# schema.net
KiCad netlist of a schematic drawn in EAGLE
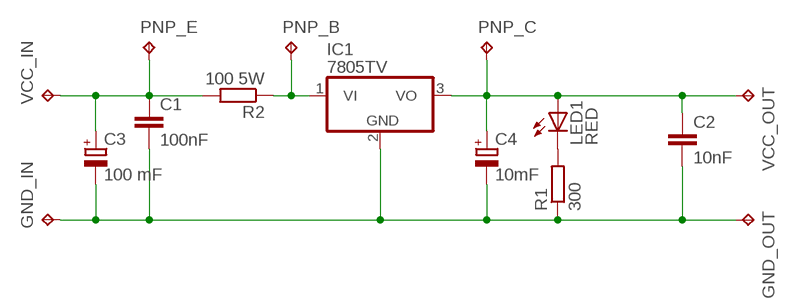
[diagram p0: schematic, sheet 1]

(export (version "E")
  (design (tool "Eeschema 10.0.6"))
  (components
    (comp (ref "C1")
      (value "100nF")
      (footprint "eagle-import:C2.5-4")
      (libsource (lib "eagle-import") (part "C2.5/4"))
    )
    (comp (ref "C2")
      (value "10nF")
      (footprint "eagle-import:C2.5-4")
      (libsource (lib "eagle-import") (part "C2.5/4"))
    )
    (comp (ref "C3")
      (value "100 mF")
      (footprint "eagle-import:E5-13")
      (libsource (lib "eagle-import") (part "CPOL-EUE5-13"))
    )
    (comp (ref "C4")
      (value "10mF")
      (footprint "eagle-import:E5-13")
      (libsource (lib "eagle-import") (part "CPOL-EUE5-13"))
    )
    (comp (ref "GND_IN")
      (value "TPPAD1-20")
      (footprint "eagle-import:P1-20")
      (libsource (lib "eagle-import") (part "TPPAD1-20"))
    )
    (comp (ref "GND_OUT")
      (value "TPPAD1-20")
      (footprint "eagle-import:P1-20")
      (libsource (lib "eagle-import") (part "TPPAD1-20"))
    )
    (comp (ref "IC1")
      (value "7805TV")
      (footprint "eagle-import:TO220V")
      (libsource (lib "eagle-import") (part "78TV05"))
    )
    (comp (ref "LED1")
      (value "RED")
      (footprint "eagle-import:LED3MM")
      (libsource (lib "eagle-import") (part "LED3MM"))
    )
    (comp (ref "PNP_B")
      (value "TPPAD1-20Y")
      (footprint "eagle-import:P1-20Y")
      (libsource (lib "eagle-import") (part "TPPAD1-20Y"))
    )
    (comp (ref "PNP_C")
      (value "TPPAD1-20Y")
      (footprint "eagle-import:P1-20Y")
      (libsource (lib "eagle-import") (part "TPPAD1-20Y"))
    )
    (comp (ref "PNP_E")
      (value "TPPAD1-20Y")
      (footprint "eagle-import:P1-20Y")
      (libsource (lib "eagle-import") (part "TPPAD1-20Y"))
    )
    (comp (ref "R1")
      (value "300")
      (footprint "eagle-import:0204V")
      (libsource (lib "eagle-import") (part "R-EU_0204/2V"))
    )
    (comp (ref "R2")
      (value "100 5W")
      (footprint "eagle-import:0204_7")
      (libsource (lib "eagle-import") (part "R-EU_0204/7"))
    )
    (comp (ref "VCC_IN")
      (value "TPPAD1-20")
      (footprint "eagle-import:P1-20")
      (libsource (lib "eagle-import") (part "TPPAD1-20"))
    )
    (comp (ref "VCC_OUT")
      (value "TPPAD1-20")
      (footprint "eagle-import:P1-20")
      (libsource (lib "eagle-import") (part "TPPAD1-20"))
    )
  )
  (nets
    (net (code "1") (name "Net-(C1-Pad1)") (class "Default")
      (node (ref "C1") (pin "1") (pinfunction "1_1") (pintype "passive"))
      (node (ref "C3") (pin "+") (pinfunction "+_+") (pintype "passive"))
      (node (ref "PNP_E") (pin "TP") (pinfunction "TP_TP") (pintype "input"))
      (node (ref "R2") (pin "2") (pinfunction "2_2") (pintype "passive"))
      (node (ref "VCC_IN") (pin "TP") (pinfunction "TP_TP") (pintype "input"))
    )
    (net (code "2") (name "Net-(IC1-GND)") (class "Default")
      (node (ref "C1") (pin "2") (pinfunction "2_2") (pintype "passive"))
      (node (ref "C2") (pin "2") (pinfunction "2_2") (pintype "passive"))
      (node (ref "C3") (pin "-") (pinfunction "-_-") (pintype "passive"))
      (node (ref "C4") (pin "-") (pinfunction "-_-") (pintype "passive"))
      (node (ref "GND_IN") (pin "TP") (pinfunction "TP_TP") (pintype "input"))
      (node (ref "GND_OUT") (pin "TP") (pinfunction "TP_TP") (pintype "input"))
      (node (ref "IC1") (pin "2") (pinfunction "GND_2") (pintype "passive"))
      (node (ref "R1") (pin "1") (pinfunction "1_1") (pintype "passive"))
    )
    (net (code "3") (name "Net-(IC1-VI)") (class "Default")
      (node (ref "IC1") (pin "1") (pinfunction "VI_1") (pintype "input"))
      (node (ref "PNP_B") (pin "TP") (pinfunction "TP_TP") (pintype "input"))
      (node (ref "R2") (pin "1") (pinfunction "1_1") (pintype "passive"))
    )
    (net (code "4") (name "Net-(IC1-VO)") (class "Default")
      (node (ref "C2") (pin "1") (pinfunction "1_1") (pintype "passive"))
      (node (ref "C4") (pin "+") (pinfunction "+_+") (pintype "passive"))
      (node (ref "IC1") (pin "3") (pinfunction "VO_3") (pintype "passive"))
      (node (ref "LED1") (pin "A") (pinfunction "A_A") (pintype "passive"))
      (node (ref "PNP_C") (pin "TP") (pinfunction "TP_TP") (pintype "input"))
      (node (ref "VCC_OUT") (pin "TP") (pinfunction "TP_TP") (pintype "input"))
    )
    (net (code "5") (name "Net-(LED1-C)") (class "Default")
      (node (ref "LED1") (pin "K") (pinfunction "C_K") (pintype "passive"))
      (node (ref "R1") (pin "2") (pinfunction "2_2") (pintype "passive"))
    )
  )
)
